# main-board.net
KiCad netlist of a schematic drawn in Altium Designer
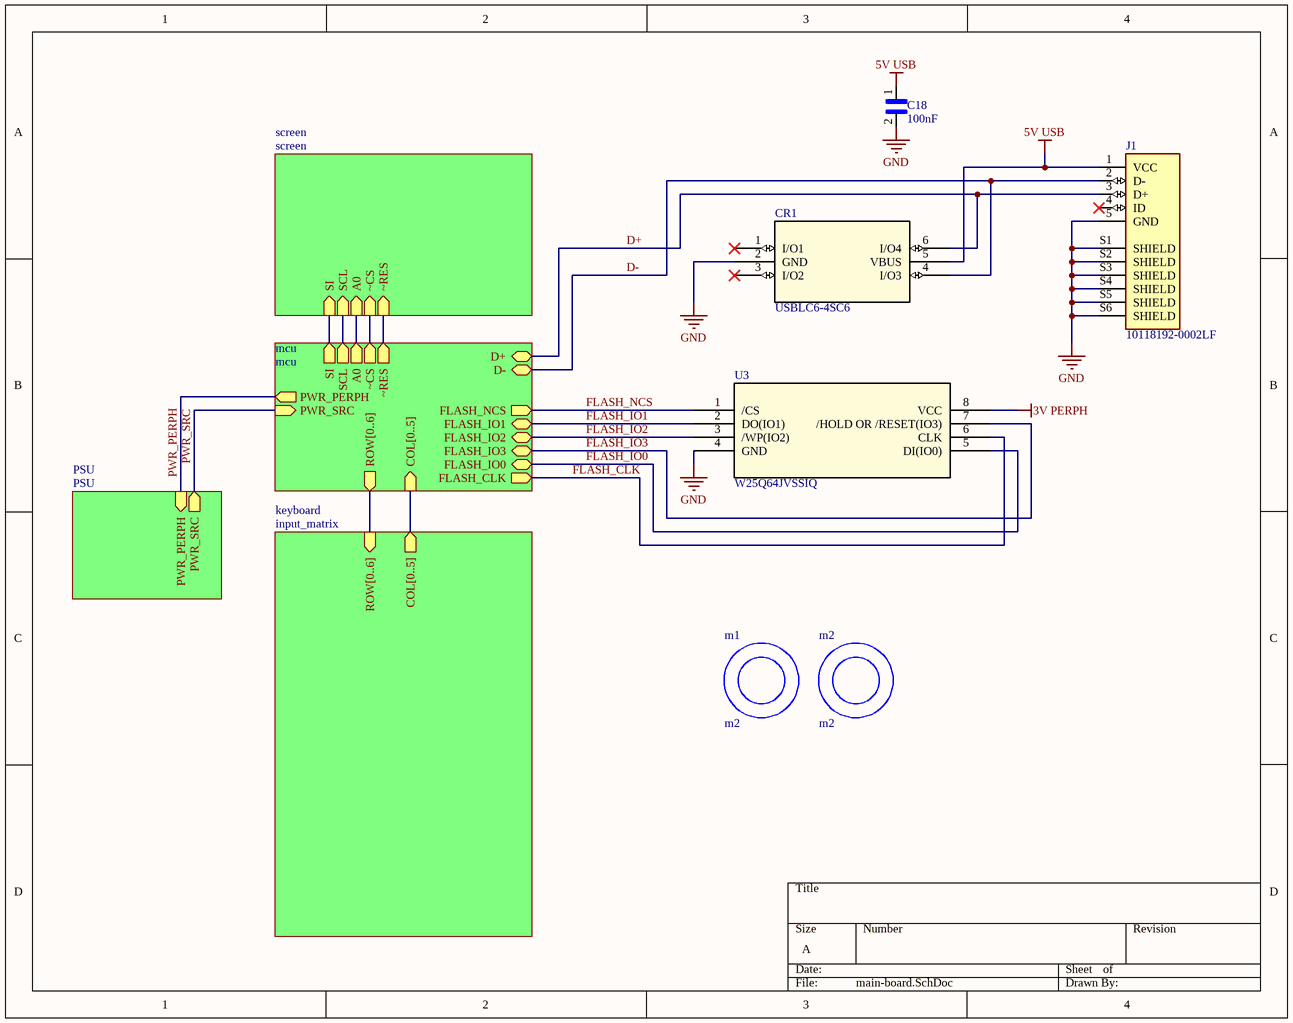
[diagram p0: main-board.SchDoc]

(export (version "E")
  (design (tool "Eeschema 10.0.6"))
  (components
    (comp (ref "C18")
      (value "100nF")
      (footprint "CAPC1005X55N")
      (description "0.1ÂµF Â±10% 10V Ceramic Capacitor X7R 0402 _1005 Metric_")
      (fields (field (name "MP") "CL05B104KP5NNNC") (field (name "MF") "Samsung Electro-Mechanics"))
      (libsource (lib "CL05B104KP5NNNC") (part "CL05B104KP5NNNC"))
    )
    (comp (ref "CR1")
      (value "USBLC6-4SC6")
      (footprint "SOT23-6L_STM")
      (description "No Description Available")
      (libsource (lib "USBLC6-4SC6") (part "USBLC6-4SC6"))
    )
    (comp (ref "J1")
      (value "10118192-0002LF")
      (footprint "AMPHENOL_10118192-0002LF")
      (description "Micro USB 2.0, Input Output Connectors, B TYPE RECEPTACLE without flange")
      (fields (field (name "MF") "Amphenol ICC"))
      (libsource (lib "10118192-0002LF") (part "10118192-0002LF"))
    )
    (comp (ref "m1") (value "m2") (footprint "m2") (libsource (lib "m2") (part "m2")))
    (comp (ref "m2") (value "m2") (footprint "m2") (libsource (lib "m2") (part "m2")))
    (comp (ref "U3")
      (value "W25Q64JVSSIQ")
      (footprint "SOIC-8_5P28X5P28_WIN")
      (description "W25Q64JVSSIQ. 64MBit Quad-SPI flash")
      (libsource (lib "W25Q64JVSSIQ") (part "W25Q64JVSSIQ"))
    )
  )
  (nets
    (net (code "3") (name "/D+") (class "Default")
      (node (ref "CR1") (pin "6") (pinfunction "I/O4_6") (pintype "bidirectional"))
      (node (ref "J1") (pin "3") (pinfunction "D+_3") (pintype "bidirectional"))
    )
    (net (code "4") (name "/D-") (class "Default")
      (node (ref "CR1") (pin "4") (pinfunction "I/O3_4") (pintype "bidirectional"))
      (node (ref "J1") (pin "2") (pinfunction "D-_2") (pintype "bidirectional"))
    )
    (net (code "5") (name "/FLASH_CLK") (class "Default")
      (node (ref "U3") (pin "6") (pinfunction "CLK_6") (pintype "passive"))
    )
    (net (code "6") (name "/FLASH_IO0") (class "Default")
      (node (ref "U3") (pin "5") (pinfunction "DI(IO0)_5") (pintype "passive"))
    )
    (net (code "7") (name "/FLASH_IO1") (class "Default")
      (node (ref "U3") (pin "2") (pinfunction "DO(IO1)_2") (pintype "passive"))
    )
    (net (code "8") (name "/FLASH_IO2") (class "Default")
      (node (ref "U3") (pin "3") (pinfunction "/WP(IO2)_3") (pintype "passive"))
    )
    (net (code "9") (name "/FLASH_IO3") (class "Default")
      (node (ref "U3") (pin "7") (pinfunction "/HOLD_OR_/RESET(IO3)_7") (pintype "passive"))
    )
    (net (code "10") (name "/FLASH_NCS") (class "Default")
      (node (ref "U3") (pin "1") (pinfunction "/CS_1") (pintype "passive"))
    )
    (net (code "18") (name "3V PERPH") (class "Default")
      (node (ref "U3") (pin "8") (pinfunction "VCC_8") (pintype "power_in"))
    )
    (net (code "19") (name "5V USB") (class "Default")
      (node (ref "C18") (pin "1") (pinfunction "1_1") (pintype "passive"))
      (node (ref "CR1") (pin "5") (pinfunction "VBUS_5") (pintype "power_in"))
      (node (ref "J1") (pin "1") (pinfunction "VCC_1") (pintype "power_in"))
    )
    (net (code "20") (name "GND") (class "Default")
      (node (ref "C18") (pin "2") (pinfunction "2_2") (pintype "passive"))
      (node (ref "CR1") (pin "2") (pinfunction "GND_2") (pintype "power_in"))
      (node (ref "J1") (pin "5") (pinfunction "GND_5") (pintype "power_in"))
      (node (ref "J1") (pin "S1") (pinfunction "SHIELD_S1") (pintype "passive"))
      (node (ref "J1") (pin "S2") (pinfunction "SHIELD_S2") (pintype "passive"))
      (node (ref "J1") (pin "S3") (pinfunction "SHIELD_S3") (pintype "passive"))
      (node (ref "J1") (pin "S4") (pinfunction "SHIELD_S4") (pintype "passive"))
      (node (ref "J1") (pin "S5") (pinfunction "SHIELD_S5") (pintype "passive"))
      (node (ref "J1") (pin "S6") (pinfunction "SHIELD_S6") (pintype "passive"))
      (node (ref "U3") (pin "4") (pinfunction "GND_4") (pintype "power_in"))
    )
    (net (code "21") (name "unconnected-(CR1-I{slash}O1-Pad1)") (class "Default")
      (node (ref "CR1") (pin "1") (pinfunction "I/O1_1") (pintype "bidirectional+no_connect"))
    )
    (net (code "22") (name "unconnected-(CR1-I{slash}O2-Pad3)") (class "Default")
      (node (ref "CR1") (pin "3") (pinfunction "I/O2_3") (pintype "bidirectional+no_connect"))
    )
    (net (code "23") (name "unconnected-(J1-ID-Pad4)") (class "Default")
      (node (ref "J1") (pin "4") (pinfunction "ID_4") (pintype "bidirectional+no_connect"))
    )
  )
)
